# PartsHunter.net
KiCad netlist of a schematic drawn in EAGLE
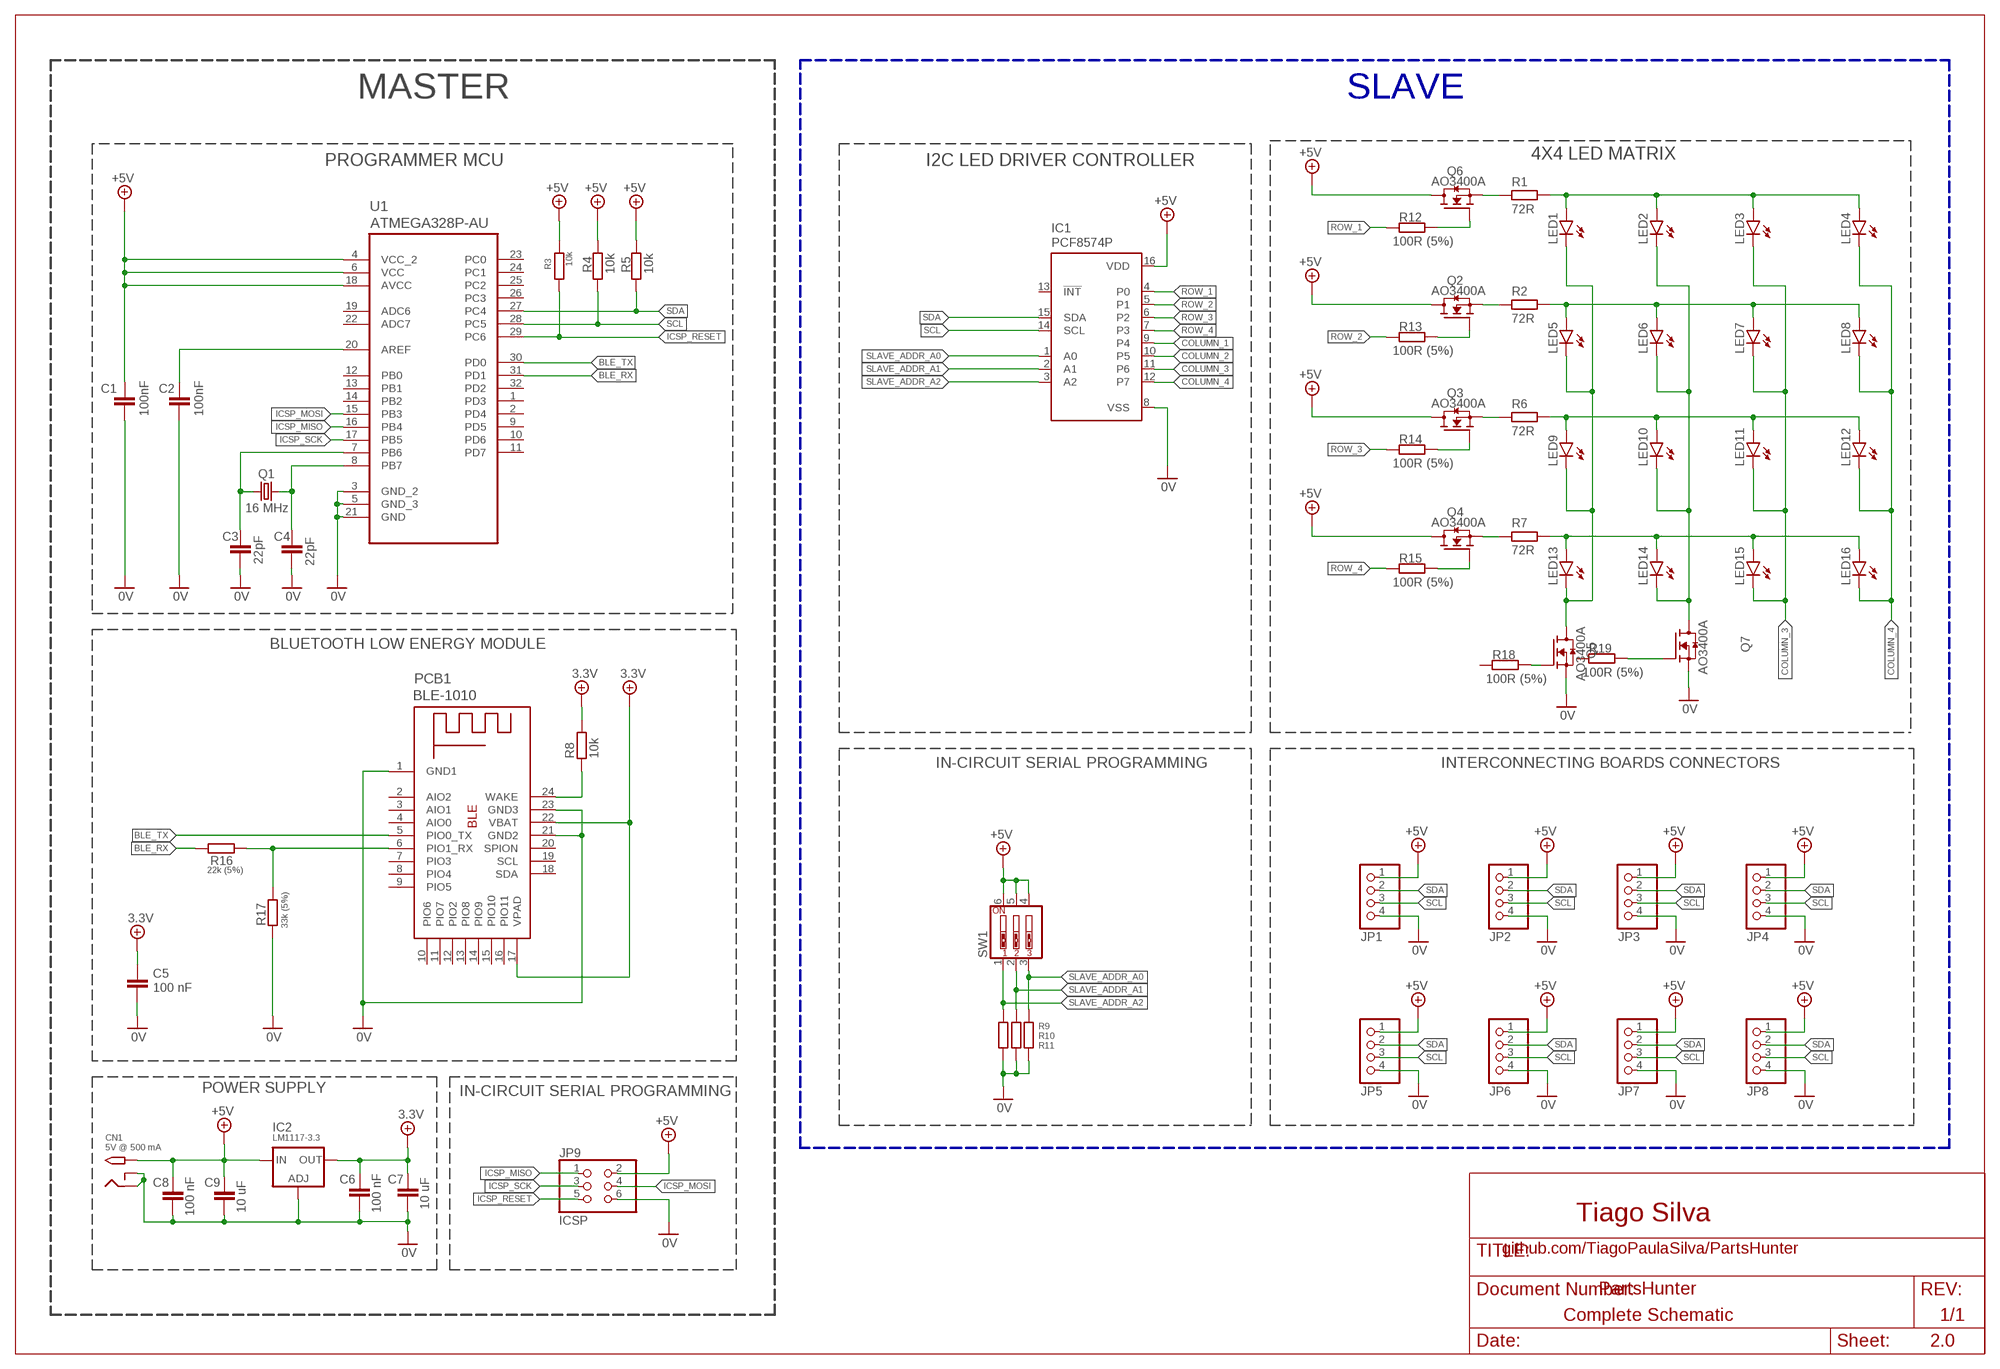
[diagram p0: schematic, sheet 1]

(export (version "E")
  (design (tool "Eeschema 10.0.6"))
  (components
    (comp (ref "C1")
      (value "100nF")
      (footprint "eagle-import:C0805")
      (libsource (lib "eagle-import") (part "C-EUC0805"))
    )
    (comp (ref "C2")
      (value "100nF")
      (footprint "eagle-import:C0805")
      (libsource (lib "eagle-import") (part "C-EUC0805"))
    )
    (comp (ref "C3")
      (value "22pF")
      (footprint "eagle-import:C0805")
      (libsource (lib "eagle-import") (part "C-EUC0805"))
    )
    (comp (ref "C4")
      (value "22pF")
      (footprint "eagle-import:C0805")
      (libsource (lib "eagle-import") (part "C-EUC0805"))
    )
    (comp (ref "C5")
      (value "100 nF")
      (footprint "eagle-import:C0805")
      (libsource (lib "eagle-import") (part "C-EUC0805"))
    )
    (comp (ref "C6")
      (value "100 nF")
      (footprint "eagle-import:C0805")
      (libsource (lib "eagle-import") (part "C-EUC0805"))
    )
    (comp (ref "C7")
      (value "10 uF")
      (footprint "eagle-import:C0805")
      (libsource (lib "eagle-import") (part "C-EUC0805"))
    )
    (comp (ref "C8")
      (value "100 nF")
      (footprint "eagle-import:C0805")
      (libsource (lib "eagle-import") (part "C-EUC0805"))
    )
    (comp (ref "C9")
      (value "10 uF")
      (footprint "eagle-import:C0805")
      (libsource (lib "eagle-import") (part "C-EUC0805"))
    )
    (comp (ref "CN1")
      (value "2.1MMJACKTHM")
      (footprint "eagle-import:PJ-102A")
      (libsource (lib "eagle-import") (part "2.1MMJACKTHM"))
    )
    (comp (ref "IC1")
      (value "PCF8574P")
      (footprint "eagle-import:DIL16")
      (fields (field (name "MPN") "PCF8574PN"))
      (libsource (lib "eagle-import") (part "PCF8574P"))
    )
    (comp (ref "IC2")
      (value "LM1117-3.3")
      (footprint "eagle-import:SOT223")
      (libsource (lib "eagle-import") (part "LD117A?S33TR"))
    )
    (comp (ref "JP1")
      (value "PINHD-1X4/90")
      (footprint "eagle-import:1X04_90")
      (libsource (lib "eagle-import") (part "PINHD-1X4/90"))
    )
    (comp (ref "JP2")
      (value "PINHD-1X4/90")
      (footprint "eagle-import:1X04_90")
      (libsource (lib "eagle-import") (part "PINHD-1X4/90"))
    )
    (comp (ref "JP3")
      (value "PINHD-1X4/90")
      (footprint "eagle-import:1X04_90")
      (libsource (lib "eagle-import") (part "PINHD-1X4/90"))
    )
    (comp (ref "JP4")
      (value "PINHD-1X4/90")
      (footprint "eagle-import:1X04_90")
      (libsource (lib "eagle-import") (part "PINHD-1X4/90"))
    )
    (comp (ref "JP5")
      (value "PINHD-1X4/90")
      (footprint "eagle-import:1X04_90")
      (libsource (lib "eagle-import") (part "PINHD-1X4/90"))
    )
    (comp (ref "JP6")
      (value "PINHD-1X4/90")
      (footprint "eagle-import:1X04_90")
      (libsource (lib "eagle-import") (part "PINHD-1X4/90"))
    )
    (comp (ref "JP7")
      (value "PINHD-1X4/90")
      (footprint "eagle-import:1X04_90")
      (libsource (lib "eagle-import") (part "PINHD-1X4/90"))
    )
    (comp (ref "JP8")
      (value "PINHD-1X4/90")
      (footprint "eagle-import:1X04_90")
      (libsource (lib "eagle-import") (part "PINHD-1X4/90"))
    )
    (comp (ref "JP9")
      (value "ICSP")
      (footprint "eagle-import:2X03")
      (libsource (lib "eagle-import") (part "PINHD-2X3"))
    )
    (comp (ref "LED1")
      (value "LEDKA-3528ASYC")
      (footprint "eagle-import:KA-3528ASYC")
      (libsource (lib "eagle-import") (part "LEDKA-3528ASYC"))
    )
    (comp (ref "LED2")
      (value "LEDKA-3528ASYC")
      (footprint "eagle-import:KA-3528ASYC")
      (libsource (lib "eagle-import") (part "LEDKA-3528ASYC"))
    )
    (comp (ref "LED3")
      (value "LEDKA-3528ASYC")
      (footprint "eagle-import:KA-3528ASYC")
      (libsource (lib "eagle-import") (part "LEDKA-3528ASYC"))
    )
    (comp (ref "LED4")
      (value "LEDKA-3528ASYC")
      (footprint "eagle-import:KA-3528ASYC")
      (libsource (lib "eagle-import") (part "LEDKA-3528ASYC"))
    )
    (comp (ref "LED5")
      (value "LEDKA-3528ASYC")
      (footprint "eagle-import:KA-3528ASYC")
      (libsource (lib "eagle-import") (part "LEDKA-3528ASYC"))
    )
    (comp (ref "LED6")
      (value "LEDKA-3528ASYC")
      (footprint "eagle-import:KA-3528ASYC")
      (libsource (lib "eagle-import") (part "LEDKA-3528ASYC"))
    )
    (comp (ref "LED7")
      (value "LEDKA-3528ASYC")
      (footprint "eagle-import:KA-3528ASYC")
      (libsource (lib "eagle-import") (part "LEDKA-3528ASYC"))
    )
    (comp (ref "LED8")
      (value "LEDKA-3528ASYC")
      (footprint "eagle-import:KA-3528ASYC")
      (libsource (lib "eagle-import") (part "LEDKA-3528ASYC"))
    )
    (comp (ref "LED9")
      (value "LEDKA-3528ASYC")
      (footprint "eagle-import:KA-3528ASYC")
      (libsource (lib "eagle-import") (part "LEDKA-3528ASYC"))
    )
    (comp (ref "LED10")
      (value "LEDKA-3528ASYC")
      (footprint "eagle-import:KA-3528ASYC")
      (libsource (lib "eagle-import") (part "LEDKA-3528ASYC"))
    )
    (comp (ref "LED11")
      (value "LEDKA-3528ASYC")
      (footprint "eagle-import:KA-3528ASYC")
      (libsource (lib "eagle-import") (part "LEDKA-3528ASYC"))
    )
    (comp (ref "LED12")
      (value "LEDKA-3528ASYC")
      (footprint "eagle-import:KA-3528ASYC")
      (libsource (lib "eagle-import") (part "LEDKA-3528ASYC"))
    )
    (comp (ref "LED13")
      (value "LEDKA-3528ASYC")
      (footprint "eagle-import:KA-3528ASYC")
      (libsource (lib "eagle-import") (part "LEDKA-3528ASYC"))
    )
    (comp (ref "LED14")
      (value "LEDKA-3528ASYC")
      (footprint "eagle-import:KA-3528ASYC")
      (libsource (lib "eagle-import") (part "LEDKA-3528ASYC"))
    )
    (comp (ref "LED15")
      (value "LEDKA-3528ASYC")
      (footprint "eagle-import:KA-3528ASYC")
      (libsource (lib "eagle-import") (part "LEDKA-3528ASYC"))
    )
    (comp (ref "LED16")
      (value "LEDKA-3528ASYC")
      (footprint "eagle-import:KA-3528ASYC")
      (libsource (lib "eagle-import") (part "LEDKA-3528ASYC"))
    )
    (comp (ref "PCB1")
      (value "BLE-1010")
      (footprint "eagle-import:BLE-1010")
      (libsource (lib "eagle-import") (part "BLE-1010"))
    )
    (comp (ref "Q1")
      (value "16 MHz")
      (footprint "eagle-import:HC49UP")
      (libsource (lib "eagle-import") (part "CRYSTALHC49UP"))
    )
    (comp (ref "Q2")
      (value "AO3400A")
      (footprint "eagle-import:SOT95P280X125-3N")
      (fields (field (name "MF") "Alpha &"))
      (libsource (lib "eagle-import") (part "AO3400A"))
    )
    (comp (ref "Q3")
      (value "AO3400A")
      (footprint "eagle-import:SOT95P280X125-3N")
      (fields (field (name "MF") "Alpha &"))
      (libsource (lib "eagle-import") (part "AO3400A"))
    )
    (comp (ref "Q4")
      (value "AO3400A")
      (footprint "eagle-import:SOT95P280X125-3N")
      (fields (field (name "MF") "Alpha &"))
      (libsource (lib "eagle-import") (part "AO3400A"))
    )
    (comp (ref "Q5")
      (value "AO3400A")
      (footprint "eagle-import:SOT95P280X125-3N")
      (fields (field (name "MF") "Alpha &"))
      (libsource (lib "eagle-import") (part "AO3400A"))
    )
    (comp (ref "Q6")
      (value "AO3400A")
      (footprint "eagle-import:SOT95P280X125-3N")
      (fields (field (name "MF") "Alpha &"))
      (libsource (lib "eagle-import") (part "AO3400A"))
    )
    (comp (ref "Q7")
      (value "AO3400A")
      (footprint "eagle-import:SOT95P280X125-3N")
      (fields (field (name "MF") "Alpha &"))
      (libsource (lib "eagle-import") (part "AO3400A"))
    )
    (comp (ref "R1")
      (value "72R")
      (footprint "eagle-import:R0805")
      (libsource (lib "eagle-import") (part "R-EU_R0805"))
    )
    (comp (ref "R2")
      (value "72R")
      (footprint "eagle-import:R0805")
      (libsource (lib "eagle-import") (part "R-EU_R0805"))
    )
    (comp (ref "R3")
      (value "10k")
      (footprint "eagle-import:R0805")
      (libsource (lib "eagle-import") (part "R-EU_R0805"))
    )
    (comp (ref "R4")
      (value "10k")
      (footprint "eagle-import:R0805")
      (libsource (lib "eagle-import") (part "R-EU_R0805"))
    )
    (comp (ref "R5")
      (value "10k")
      (footprint "eagle-import:R0805")
      (libsource (lib "eagle-import") (part "R-EU_R0805"))
    )
    (comp (ref "R6")
      (value "72R")
      (footprint "eagle-import:R0805")
      (libsource (lib "eagle-import") (part "R-EU_R0805"))
    )
    (comp (ref "R7")
      (value "72R")
      (footprint "eagle-import:R0805")
      (libsource (lib "eagle-import") (part "R-EU_R0805"))
    )
    (comp (ref "R8")
      (value "10k")
      (footprint "eagle-import:R0603")
      (libsource (lib "eagle-import") (part "R-EU_R0603"))
    )
    (comp (ref "R9")
      (value "10k")
      (footprint "eagle-import:R0805")
      (libsource (lib "eagle-import") (part "R-EU_R0805"))
    )
    (comp (ref "R10")
      (value "10k")
      (footprint "eagle-import:R0805")
      (libsource (lib "eagle-import") (part "R-EU_R0805"))
    )
    (comp (ref "R11")
      (value "10k")
      (footprint "eagle-import:R0805")
      (libsource (lib "eagle-import") (part "R-EU_R0805"))
    )
    (comp (ref "R12")
      (value "100R (5%)")
      (footprint "eagle-import:R0805")
      (libsource (lib "eagle-import") (part "R-EU_R0805"))
    )
    (comp (ref "R13")
      (value "100R (5%)")
      (footprint "eagle-import:R0805")
      (libsource (lib "eagle-import") (part "R-EU_R0805"))
    )
    (comp (ref "R14")
      (value "100R (5%)")
      (footprint "eagle-import:R0805")
      (libsource (lib "eagle-import") (part "R-EU_R0805"))
    )
    (comp (ref "R15")
      (value "100R (5%)")
      (footprint "eagle-import:R0805")
      (libsource (lib "eagle-import") (part "R-EU_R0805"))
    )
    (comp (ref "R16")
      (value "22k (5%)")
      (footprint "eagle-import:R0805")
      (libsource (lib "eagle-import") (part "R-EU_R0805"))
    )
    (comp (ref "R17")
      (value "33k (5%)")
      (footprint "eagle-import:R0805")
      (libsource (lib "eagle-import") (part "R-EU_R0805"))
    )
    (comp (ref "R18")
      (value "100R (5%)")
      (footprint "eagle-import:R0805")
      (libsource (lib "eagle-import") (part "R-EU_R0805"))
    )
    (comp (ref "R19")
      (value "100R (5%)")
      (footprint "eagle-import:R0805")
      (libsource (lib "eagle-import") (part "R-EU_R0805"))
    )
    (comp (ref "SW1")
      (value "SW_DIP-3")
      (footprint "eagle-import:EDG-03")
      (libsource (lib "eagle-import") (part "SW_DIP-3"))
    )
    (comp (ref "U1")
      (value "ATMEGA328P-AU")
      (footprint "eagle-import:QFP80P900X900X120-32N")
      (libsource (lib "eagle-import") (part "ATMEGA328P-AU"))
    )
  )
  (nets
    (net (code "1") (name "+5V") (class "Default")
      (node (ref "C1") (pin "2") (pinfunction "2_2") (pintype "passive"))
      (node (ref "C8") (pin "1") (pinfunction "1_1") (pintype "passive"))
      (node (ref "C9") (pin "1") (pinfunction "1_1") (pintype "passive"))
      (node (ref "CN1") (pin "TIP") (pinfunction "TIP_TIP") (pintype "bidirectional"))
      (node (ref "IC1") (pin "16") (pinfunction "VDD_16") (pintype "power_in"))
      (node (ref "IC2") (pin "3") (pinfunction "IN_3") (pintype "input"))
      (node (ref "JP1") (pin "1") (pinfunction "1_1") (pintype "passive"))
      (node (ref "JP2") (pin "1") (pinfunction "1_1") (pintype "passive"))
      (node (ref "JP3") (pin "1") (pinfunction "1_1") (pintype "passive"))
      (node (ref "JP4") (pin "1") (pinfunction "1_1") (pintype "passive"))
      (node (ref "JP5") (pin "1") (pinfunction "1_1") (pintype "passive"))
      (node (ref "JP6") (pin "1") (pinfunction "1_1") (pintype "passive"))
      (node (ref "JP7") (pin "1") (pinfunction "1_1") (pintype "passive"))
      (node (ref "JP8") (pin "1") (pinfunction "1_1") (pintype "passive"))
      (node (ref "JP9") (pin "2") (pinfunction "2_2") (pintype "passive"))
      (node (ref "Q2") (pin "3") (pinfunction "D_3") (pintype "passive"))
      (node (ref "Q3") (pin "3") (pinfunction "D_3") (pintype "passive"))
      (node (ref "Q4") (pin "3") (pinfunction "D_3") (pintype "passive"))
      (node (ref "Q6") (pin "3") (pinfunction "D_3") (pintype "passive"))
      (node (ref "R3") (pin "1") (pinfunction "1_1") (pintype "passive"))
      (node (ref "R4") (pin "1") (pinfunction "1_1") (pintype "passive"))
      (node (ref "R5") (pin "1") (pinfunction "1_1") (pintype "passive"))
      (node (ref "SW1") (pin "4") (pinfunction "4_4") (pintype "passive"))
      (node (ref "SW1") (pin "5") (pinfunction "5_5") (pintype "passive"))
      (node (ref "SW1") (pin "6") (pinfunction "6_6") (pintype "passive"))
      (node (ref "U1") (pin "18") (pinfunction "AVCC_18") (pintype "power_in"))
      (node (ref "U1") (pin "4") (pinfunction "VCC_2_4") (pintype "power_in"))
      (node (ref "U1") (pin "6") (pinfunction "VCC_6") (pintype "power_in"))
    )
    (net (code "2") (name "0V") (class "Default")
      (node (ref "C1") (pin "1") (pinfunction "1_1") (pintype "passive"))
      (node (ref "C2") (pin "1") (pinfunction "1_1") (pintype "passive"))
      (node (ref "C3") (pin "1") (pinfunction "1_1") (pintype "passive"))
      (node (ref "C4") (pin "1") (pinfunction "1_1") (pintype "passive"))
      (node (ref "C5") (pin "2") (pinfunction "2_2") (pintype "passive"))
      (node (ref "C6") (pin "2") (pinfunction "2_2") (pintype "passive"))
      (node (ref "C7") (pin "2") (pinfunction "2_2") (pintype "passive"))
      (node (ref "C8") (pin "2") (pinfunction "2_2") (pintype "passive"))
      (node (ref "C9") (pin "2") (pinfunction "2_2") (pintype "passive"))
      (node (ref "CN1") (pin "RING") (pinfunction "RING_RING") (pintype "bidirectional"))
      (node (ref "CN1") (pin "RING_SW") (pinfunction "RING_SW_RING_SW") (pintype "bidirectional"))
      (node (ref "IC1") (pin "8") (pinfunction "VSS_8") (pintype "power_in"))
      (node (ref "IC2") (pin "1") (pinfunction "ADJ_1") (pintype "input"))
      (node (ref "JP1") (pin "4") (pinfunction "4_4") (pintype "passive"))
      (node (ref "JP2") (pin "4") (pinfunction "4_4") (pintype "passive"))
      (node (ref "JP3") (pin "4") (pinfunction "4_4") (pintype "passive"))
      (node (ref "JP4") (pin "4") (pinfunction "4_4") (pintype "passive"))
      (node (ref "JP5") (pin "4") (pinfunction "4_4") (pintype "passive"))
      (node (ref "JP6") (pin "4") (pinfunction "4_4") (pintype "passive"))
      (node (ref "JP7") (pin "4") (pinfunction "4_4") (pintype "passive"))
      (node (ref "JP8") (pin "4") (pinfunction "4_4") (pintype "passive"))
      (node (ref "JP9") (pin "6") (pinfunction "6_6") (pintype "passive"))
      (node (ref "PCB1") (pin "1") (pinfunction "GND1_1") (pintype "power_in"))
      (node (ref "PCB1") (pin "21") (pinfunction "GND2_21") (pintype "power_in"))
      (node (ref "PCB1") (pin "23") (pinfunction "GND3_23") (pintype "power_in"))
      (node (ref "Q5") (pin "2") (pinfunction "S_2") (pintype "passive"))
      (node (ref "Q7") (pin "2") (pinfunction "S_2") (pintype "passive"))
      (node (ref "R10") (pin "2") (pinfunction "2_2") (pintype "passive"))
      (node (ref "R11") (pin "2") (pinfunction "2_2") (pintype "passive"))
      (node (ref "R17") (pin "1") (pinfunction "1_1") (pintype "passive"))
      (node (ref "R9") (pin "2") (pinfunction "2_2") (pintype "passive"))
      (node (ref "U1") (pin "21") (pinfunction "GND_21") (pintype "passive"))
      (node (ref "U1") (pin "3") (pinfunction "GND_2_3") (pintype "passive"))
      (node (ref "U1") (pin "5") (pinfunction "GND_3_5") (pintype "passive"))
    )
    (net (code "3") (name "3.3V") (class "Default")
      (node (ref "C5") (pin "1") (pinfunction "1_1") (pintype "passive"))
      (node (ref "C6") (pin "1") (pinfunction "1_1") (pintype "passive"))
      (node (ref "C7") (pin "1") (pinfunction "1_1") (pintype "passive"))
      (node (ref "IC2") (pin "4") (pinfunction "OUT_4") (pintype "passive"))
      (node (ref "PCB1") (pin "17") (pinfunction "VPAD_17") (pintype "bidirectional"))
      (node (ref "PCB1") (pin "22") (pinfunction "VBAT_22") (pintype "power_in"))
      (node (ref "R8") (pin "1") (pinfunction "1_1") (pintype "passive"))
    )
    (net (code "4") (name "BLE_RX") (class "Default")
      (node (ref "R16") (pin "1") (pinfunction "1_1") (pintype "passive"))
      (node (ref "U1") (pin "31") (pinfunction "PD1_31") (pintype "bidirectional"))
    )
    (net (code "5") (name "BLE_TX") (class "Default")
      (node (ref "PCB1") (pin "5") (pinfunction "PIO0_TX_5") (pintype "bidirectional"))
      (node (ref "U1") (pin "30") (pinfunction "PD0_30") (pintype "bidirectional"))
    )
    (net (code "6") (name "COLUMN_1") (class "Default")
      (node (ref "IC1") (pin "9") (pinfunction "P4_9") (pintype "bidirectional"))
      (node (ref "LED1") (pin "C") (pinfunction "C_C") (pintype "passive"))
      (node (ref "LED1") (pin "P$2") (pinfunction "C_P$2") (pintype "passive"))
      (node (ref "LED13") (pin "C") (pinfunction "C_C") (pintype "passive"))
      (node (ref "LED13") (pin "P$2") (pinfunction "C_P$2") (pintype "passive"))
      (node (ref "LED5") (pin "C") (pinfunction "C_C") (pintype "passive"))
      (node (ref "LED5") (pin "P$2") (pinfunction "C_P$2") (pintype "passive"))
      (node (ref "LED9") (pin "C") (pinfunction "C_C") (pintype "passive"))
      (node (ref "LED9") (pin "P$2") (pinfunction "C_P$2") (pintype "passive"))
      (node (ref "Q5") (pin "3") (pinfunction "D_3") (pintype "passive"))
    )
    (net (code "7") (name "COLUMN_2") (class "Default")
      (node (ref "IC1") (pin "10") (pinfunction "P5_10") (pintype "bidirectional"))
      (node (ref "LED10") (pin "C") (pinfunction "C_C") (pintype "passive"))
      (node (ref "LED10") (pin "P$2") (pinfunction "C_P$2") (pintype "passive"))
      (node (ref "LED14") (pin "C") (pinfunction "C_C") (pintype "passive"))
      (node (ref "LED14") (pin "P$2") (pinfunction "C_P$2") (pintype "passive"))
      (node (ref "LED2") (pin "C") (pinfunction "C_C") (pintype "passive"))
      (node (ref "LED2") (pin "P$2") (pinfunction "C_P$2") (pintype "passive"))
      (node (ref "LED6") (pin "C") (pinfunction "C_C") (pintype "passive"))
      (node (ref "LED6") (pin "P$2") (pinfunction "C_P$2") (pintype "passive"))
      (node (ref "Q7") (pin "3") (pinfunction "D_3") (pintype "passive"))
    )
    (net (code "8") (name "COLUMN_3") (class "Default")
      (node (ref "IC1") (pin "11") (pinfunction "P6_11") (pintype "bidirectional"))
      (node (ref "LED11") (pin "C") (pinfunction "C_C") (pintype "passive"))
      (node (ref "LED11") (pin "P$2") (pinfunction "C_P$2") (pintype "passive"))
      (node (ref "LED15") (pin "C") (pinfunction "C_C") (pintype "passive"))
      (node (ref "LED15") (pin "P$2") (pinfunction "C_P$2") (pintype "passive"))
      (node (ref "LED3") (pin "C") (pinfunction "C_C") (pintype "passive"))
      (node (ref "LED3") (pin "P$2") (pinfunction "C_P$2") (pintype "passive"))
      (node (ref "LED7") (pin "C") (pinfunction "C_C") (pintype "passive"))
      (node (ref "LED7") (pin "P$2") (pinfunction "C_P$2") (pintype "passive"))
    )
    (net (code "9") (name "COLUMN_4") (class "Default")
      (node (ref "IC1") (pin "12") (pinfunction "P7_12") (pintype "bidirectional"))
      (node (ref "LED12") (pin "C") (pinfunction "C_C") (pintype "passive"))
      (node (ref "LED12") (pin "P$2") (pinfunction "C_P$2") (pintype "passive"))
      (node (ref "LED16") (pin "C") (pinfunction "C_C") (pintype "passive"))
      (node (ref "LED16") (pin "P$2") (pinfunction "C_P$2") (pintype "passive"))
      (node (ref "LED4") (pin "C") (pinfunction "C_C") (pintype "passive"))
      (node (ref "LED4") (pin "P$2") (pinfunction "C_P$2") (pintype "passive"))
      (node (ref "LED8") (pin "C") (pinfunction "C_C") (pintype "passive"))
      (node (ref "LED8") (pin "P$2") (pinfunction "C_P$2") (pintype "passive"))
    )
    (net (code "10") (name "ICSP_MISO") (class "Default")
      (node (ref "JP9") (pin "1") (pinfunction "1_1") (pintype "passive"))
      (node (ref "U1") (pin "16") (pinfunction "PB4_16") (pintype "bidirectional"))
    )
    (net (code "11") (name "ICSP_MOSI") (class "Default")
      (node (ref "JP9") (pin "4") (pinfunction "4_4") (pintype "passive"))
      (node (ref "U1") (pin "15") (pinfunction "PB3_15") (pintype "bidirectional"))
    )
    (net (code "12") (name "ICSP_RESET") (class "Default")
      (node (ref "JP9") (pin "5") (pinfunction "5_5") (pintype "passive"))
      (node (ref "R3") (pin "2") (pinfunction "2_2") (pintype "passive"))
      (node (ref "U1") (pin "29") (pinfunction "PC6_29") (pintype "bidirectional"))
    )
    (net (code "13") (name "ICSP_SCK") (class "Default")
      (node (ref "JP9") (pin "3") (pinfunction "3_3") (pintype "passive"))
      (node (ref "U1") (pin "17") (pinfunction "PB5_17") (pintype "bidirectional"))
    )
    (net (code "14") (name "Net-(LED1-A-PadP$1)") (class "Default")
      (node (ref "LED1") (pin "A") (pinfunction "A_A") (pintype "passive"))
      (node (ref "LED1") (pin "P$1") (pinfunction "A_P$1") (pintype "passive"))
      (node (ref "LED2") (pin "A") (pinfunction "A_A") (pintype "passive"))
      (node (ref "LED2") (pin "P$1") (pinfunction "A_P$1") (pintype "passive"))
      (node (ref "LED3") (pin "A") (pinfunction "A_A") (pintype "passive"))
      (node (ref "LED3") (pin "P$1") (pinfunction "A_P$1") (pintype "passive"))
      (node (ref "LED4") (pin "A") (pinfunction "A_A") (pintype "passive"))
      (node (ref "LED4") (pin "P$1") (pinfunction "A_P$1") (pintype "passive"))
      (node (ref "R1") (pin "1") (pinfunction "1_1") (pintype "passive"))
    )
    (net (code "15") (name "Net-(LED5-A-PadP$1)") (class "Default")
      (node (ref "LED5") (pin "A") (pinfunction "A_A") (pintype "passive"))
      (node (ref "LED5") (pin "P$1") (pinfunction "A_P$1") (pintype "passive"))
      (node (ref "LED6") (pin "A") (pinfunction "A_A") (pintype "passive"))
      (node (ref "LED6") (pin "P$1") (pinfunction "A_P$1") (pintype "passive"))
      (node (ref "LED7") (pin "A") (pinfunction "A_A") (pintype "passive"))
      (node (ref "LED7") (pin "P$1") (pinfunction "A_P$1") (pintype "passive"))
      (node (ref "LED8") (pin "A") (pinfunction "A_A") (pintype "passive"))
      (node (ref "LED8") (pin "P$1") (pinfunction "A_P$1") (pintype "passive"))
      (node (ref "R2") (pin "1") (pinfunction "1_1") (pintype "passive"))
    )
    (net (code "16") (name "Net-(LED10-A-PadP$1)") (class "Default")
      (node (ref "LED10") (pin "A") (pinfunction "A_A") (pintype "passive"))
      (node (ref "LED10") (pin "P$1") (pinfunction "A_P$1") (pintype "passive"))
      (node (ref "LED11") (pin "A") (pinfunction "A_A") (pintype "passive"))
      (node (ref "LED11") (pin "P$1") (pinfunction "A_P$1") (pintype "passive"))
      (node (ref "LED12") (pin "A") (pinfunction "A_A") (pintype "passive"))
      (node (ref "LED12") (pin "P$1") (pinfunction "A_P$1") (pintype "passive"))
      (node (ref "LED9") (pin "A") (pinfunction "A_A") (pintype "passive"))
      (node (ref "LED9") (pin "P$1") (pinfunction "A_P$1") (pintype "passive"))
      (node (ref "R6") (pin "1") (pinfunction "1_1") (pintype "passive"))
    )
    (net (code "17") (name "Net-(LED13-A-PadP$1)") (class "Default")
      (node (ref "LED13") (pin "A") (pinfunction "A_A") (pintype "passive"))
      (node (ref "LED13") (pin "P$1") (pinfunction "A_P$1") (pintype "passive"))
      (node (ref "LED14") (pin "A") (pinfunction "A_A") (pintype "passive"))
      (node (ref "LED14") (pin "P$1") (pinfunction "A_P$1") (pintype "passive"))
      (node (ref "LED15") (pin "A") (pinfunction "A_A") (pintype "passive"))
      (node (ref "LED15") (pin "P$1") (pinfunction "A_P$1") (pintype "passive"))
      (node (ref "LED16") (pin "A") (pinfunction "A_A") (pintype "passive"))
      (node (ref "LED16") (pin "P$1") (pinfunction "A_P$1") (pintype "passive"))
      (node (ref "R7") (pin "1") (pinfunction "1_1") (pintype "passive"))
    )
    (net (code "18") (name "Net-(PCB1-PIO1_RX)") (class "Default")
      (node (ref "PCB1") (pin "6") (pinfunction "PIO1_RX_6") (pintype "bidirectional"))
      (node (ref "R16") (pin "2") (pinfunction "2_2") (pintype "passive"))
      (node (ref "R17") (pin "2") (pinfunction "2_2") (pintype "passive"))
    )
    (net (code "19") (name "Net-(PCB1-WAKE)") (class "Default")
      (node (ref "PCB1") (pin "24") (pinfunction "WAKE_24") (pintype "input"))
      (node (ref "R8") (pin "2") (pinfunction "2_2") (pintype "passive"))
    )
    (net (code "20") (name "Net-(Q2-G)") (class "Default")
      (node (ref "Q2") (pin "1") (pinfunction "G_1") (pintype "passive"))
      (node (ref "R13") (pin "2") (pinfunction "2_2") (pintype "passive"))
    )
    (net (code "21") (name "Net-(Q2-S)") (class "Default")
      (node (ref "Q2") (pin "2") (pinfunction "S_2") (pintype "passive"))
      (node (ref "R2") (pin "2") (pinfunction "2_2") (pintype "passive"))
    )
    (net (code "22") (name "Net-(Q3-G)") (class "Default")
      (node (ref "Q3") (pin "1") (pinfunction "G_1") (pintype "passive"))
      (node (ref "R14") (pin "2") (pinfunction "2_2") (pintype "passive"))
    )
    (net (code "23") (name "Net-(Q3-S)") (class "Default")
      (node (ref "Q3") (pin "2") (pinfunction "S_2") (pintype "passive"))
      (node (ref "R6") (pin "2") (pinfunction "2_2") (pintype "passive"))
    )
    (net (code "24") (name "Net-(Q4-G)") (class "Default")
      (node (ref "Q4") (pin "1") (pinfunction "G_1") (pintype "passive"))
      (node (ref "R15") (pin "2") (pinfunction "2_2") (pintype "passive"))
    )
    (net (code "25") (name "Net-(Q4-S)") (class "Default")
      (node (ref "Q4") (pin "2") (pinfunction "S_2") (pintype "passive"))
      (node (ref "R7") (pin "2") (pinfunction "2_2") (pintype "passive"))
    )
    (net (code "26") (name "Net-(Q5-G)") (class "Default")
      (node (ref "Q5") (pin "1") (pinfunction "G_1") (pintype "passive"))
      (node (ref "R18") (pin "2") (pinfunction "2_2") (pintype "passive"))
    )
    (net (code "27") (name "Net-(Q6-G)") (class "Default")
      (node (ref "Q6") (pin "1") (pinfunction "G_1") (pintype "passive"))
      (node (ref "R12") (pin "2") (pinfunction "2_2") (pintype "passive"))
    )
    (net (code "28") (name "Net-(Q6-S)") (class "Default")
      (node (ref "Q6") (pin "2") (pinfunction "S_2") (pintype "passive"))
      (node (ref "R1") (pin "2") (pinfunction "2_2") (pintype "passive"))
    )
    (net (code "29") (name "Net-(Q7-G)") (class "Default")
      (node (ref "Q7") (pin "1") (pinfunction "G_1") (pintype "passive"))
      (node (ref "R19") (pin "2") (pinfunction "2_2") (pintype "passive"))
    )
    (net (code "30") (name "Net-(U1-AREF)") (class "Default")
      (node (ref "C2") (pin "2") (pinfunction "2_2") (pintype "passive"))
      (node (ref "U1") (pin "20") (pinfunction "AREF_20") (pintype "input"))
    )
    (net (code "31") (name "Net-(U1-PB6)") (class "Default")
      (node (ref "C3") (pin "2") (pinfunction "2_2") (pintype "passive"))
      (node (ref "Q1") (pin "1") (pinfunction "1_1") (pintype "passive"))
      (node (ref "U1") (pin "7") (pinfunction "PB6_7") (pintype "bidirectional"))
    )
    (net (code "32") (name "Net-(U1-PB7)") (class "Default")
      (node (ref "C4") (pin "2") (pinfunction "2_2") (pintype "passive"))
      (node (ref "Q1") (pin "2") (pinfunction "2_2") (pintype "passive"))
      (node (ref "U1") (pin "8") (pinfunction "PB7_8") (pintype "bidirectional"))
    )
    (net (code "33") (name "ROW_1") (class "Default")
      (node (ref "IC1") (pin "4") (pinfunction "P0_4") (pintype "bidirectional"))
      (node (ref "R12") (pin "1") (pinfunction "1_1") (pintype "passive"))
    )
    (net (code "34") (name "ROW_2") (class "Default")
      (node (ref "IC1") (pin "5") (pinfunction "P1_5") (pintype "bidirectional"))
      (node (ref "R13") (pin "1") (pinfunction "1_1") (pintype "passive"))
    )
    (net (code "35") (name "ROW_3") (class "Default")
      (node (ref "IC1") (pin "6") (pinfunction "P2_6") (pintype "bidirectional"))
      (node (ref "R14") (pin "1") (pinfunction "1_1") (pintype "passive"))
    )
    (net (code "36") (name "ROW_4") (class "Default")
      (node (ref "IC1") (pin "7") (pinfunction "P3_7") (pintype "bidirectional"))
      (node (ref "R15") (pin "1") (pinfunction "1_1") (pintype "passive"))
    )
    (net (code "37") (name "SCL") (class "Default")
      (node (ref "IC1") (pin "14") (pinfunction "SCL_14") (pintype "input"))
      (node (ref "JP1") (pin "3") (pinfunction "3_3") (pintype "passive"))
      (node (ref "JP2") (pin "3") (pinfunction "3_3") (pintype "passive"))
      (node (ref "JP3") (pin "3") (pinfunction "3_3") (pintype "passive"))
      (node (ref "JP4") (pin "3") (pinfunction "3_3") (pintype "passive"))
      (node (ref "JP5") (pin "3") (pinfunction "3_3") (pintype "passive"))
      (node (ref "JP6") (pin "3") (pinfunction "3_3") (pintype "passive"))
      (node (ref "JP7") (pin "3") (pinfunction "3_3") (pintype "passive"))
      (node (ref "JP8") (pin "3") (pinfunction "3_3") (pintype "passive"))
      (node (ref "R4") (pin "2") (pinfunction "2_2") (pintype "passive"))
      (node (ref "U1") (pin "28") (pinfunction "PC5_28") (pintype "bidirectional"))
    )
    (net (code "38") (name "SDA") (class "Default")
      (node (ref "IC1") (pin "15") (pinfunction "SDA_15") (pintype "bidirectional"))
      (node (ref "JP1") (pin "2") (pinfunction "2_2") (pintype "passive"))
      (node (ref "JP2") (pin "2") (pinfunction "2_2") (pintype "passive"))
      (node (ref "JP3") (pin "2") (pinfunction "2_2") (pintype "passive"))
      (node (ref "JP4") (pin "2") (pinfunction "2_2") (pintype "passive"))
      (node (ref "JP5") (pin "2") (pinfunction "2_2") (pintype "passive"))
      (node (ref "JP6") (pin "2") (pinfunction "2_2") (pintype "passive"))
      (node (ref "JP7") (pin "2") (pinfunction "2_2") (pintype "passive"))
      (node (ref "JP8") (pin "2") (pinfunction "2_2") (pintype "passive"))
      (node (ref "R5") (pin "2") (pinfunction "2_2") (pintype "passive"))
      (node (ref "U1") (pin "27") (pinfunction "PC4_27") (pintype "bidirectional"))
    )
    (net (code "39") (name "SLAVE_ADDR_A0") (class "Default")
      (node (ref "IC1") (pin "1") (pinfunction "A0_1") (pintype "input"))
      (node (ref "R11") (pin "1") (pinfunction "1_1") (pintype "passive"))
      (node (ref "SW1") (pin "3") (pinfunction "3_3") (pintype "passive"))
    )
    (net (code "40") (name "SLAVE_ADDR_A1") (class "Default")
      (node (ref "IC1") (pin "2") (pinfunction "A1_2") (pintype "input"))
      (node (ref "R10") (pin "1") (pinfunction "1_1") (pintype "passive"))
      (node (ref "SW1") (pin "2") (pinfunction "2_2") (pintype "passive"))
    )
    (net (code "41") (name "SLAVE_ADDR_A2") (class "Default")
      (node (ref "IC1") (pin "3") (pinfunction "A2_3") (pintype "input"))
      (node (ref "R9") (pin "1") (pinfunction "1_1") (pintype "passive"))
      (node (ref "SW1") (pin "1") (pinfunction "1_1") (pintype "passive"))
    )
    (net (code "42") (name "unconnected-(IC1-~{INT}-Pad13)") (class "Default")
      (node (ref "IC1") (pin "13") (pinfunction "~{INT}_13") (pintype "output"))
    )
    (net (code "43") (name "unconnected-(PCB1-AIO0-Pad4)") (class "Default")
      (node (ref "PCB1") (pin "4") (pinfunction "AIO0_4") (pintype "bidirectional"))
    )
    (net (code "44") (name "unconnected-(PCB1-AIO1-Pad3)") (class "Default")
      (node (ref "PCB1") (pin "3") (pinfunction "AIO1_3") (pintype "bidirectional"))
    )
    (net (code "45") (name "unconnected-(PCB1-AIO2-Pad2)") (class "Default")
      (node (ref "PCB1") (pin "2") (pinfunction "AIO2_2") (pintype "bidirectional"))
    )
    (net (code "46") (name "unconnected-(PCB1-PIO2-Pad12)") (class "Default")
      (node (ref "PCB1") (pin "12") (pinfunction "PIO2_12") (pintype "bidirectional"))
    )
    (net (code "47") (name "unconnected-(PCB1-PIO3-Pad7)") (class "Default")
      (node (ref "PCB1") (pin "7") (pinfunction "PIO3_7") (pintype "bidirectional"))
    )
    (net (code "48") (name "unconnected-(PCB1-PIO4-Pad8)") (class "Default")
      (node (ref "PCB1") (pin "8") (pinfunction "PIO4_8") (pintype "bidirectional"))
    )
    (net (code "49") (name "unconnected-(PCB1-PIO5-Pad9)") (class "Default")
      (node (ref "PCB1") (pin "9") (pinfunction "PIO5_9") (pintype "bidirectional"))
    )
    (net (code "50") (name "unconnected-(PCB1-PIO6-Pad10)") (class "Default")
      (node (ref "PCB1") (pin "10") (pinfunction "PIO6_10") (pintype "bidirectional"))
    )
    (net (code "51") (name "unconnected-(PCB1-PIO7-Pad11)") (class "Default")
      (node (ref "PCB1") (pin "11") (pinfunction "PIO7_11") (pintype "bidirectional"))
    )
    (net (code "52") (name "unconnected-(PCB1-PIO8-Pad13)") (class "Default")
      (node (ref "PCB1") (pin "13") (pinfunction "PIO8_13") (pintype "bidirectional"))
    )
    (net (code "53") (name "unconnected-(PCB1-PIO9-Pad14)") (class "Default")
      (node (ref "PCB1") (pin "14") (pinfunction "PIO9_14") (pintype "bidirectional"))
    )
    (net (code "54") (name "unconnected-(PCB1-PIO10-Pad15)") (class "Default")
      (node (ref "PCB1") (pin "15") (pinfunction "PIO10_15") (pintype "bidirectional"))
    )
    (net (code "55") (name "unconnected-(PCB1-PIO11-Pad16)") (class "Default")
      (node (ref "PCB1") (pin "16") (pinfunction "PIO11_16") (pintype "bidirectional"))
    )
    (net (code "56") (name "unconnected-(PCB1-SCL-Pad19)") (class "Default")
      (node (ref "PCB1") (pin "19") (pinfunction "SCL_19") (pintype "bidirectional"))
    )
    (net (code "57") (name "unconnected-(PCB1-SDA-Pad18)") (class "Default")
      (node (ref "PCB1") (pin "18") (pinfunction "SDA_18") (pintype "bidirectional"))
    )
    (net (code "58") (name "unconnected-(PCB1-SPION-Pad20)") (class "Default")
      (node (ref "PCB1") (pin "20") (pinfunction "SPION_20") (pintype "bidirectional"))
    )
    (net (code "59") (name "unconnected-(R18-Pad1)") (class "Default")
      (node (ref "R18") (pin "1") (pinfunction "1_1") (pintype "passive"))
    )
    (net (code "60") (name "unconnected-(R19-Pad1)") (class "Default")
      (node (ref "R19") (pin "1") (pinfunction "1_1") (pintype "passive"))
    )
    (net (code "61") (name "unconnected-(U1-ADC6-Pad19)") (class "Default")
      (node (ref "U1") (pin "19") (pinfunction "ADC6_19") (pintype "input"))
    )
    (net (code "62") (name "unconnected-(U1-ADC7-Pad22)") (class "Default")
      (node (ref "U1") (pin "22") (pinfunction "ADC7_22") (pintype "input"))
    )
    (net (code "63") (name "unconnected-(U1-PB0-Pad12)") (class "Default")
      (node (ref "U1") (pin "12") (pinfunction "PB0_12") (pintype "bidirectional"))
    )
    (net (code "64") (name "unconnected-(U1-PB1-Pad13)") (class "Default")
      (node (ref "U1") (pin "13") (pinfunction "PB1_13") (pintype "bidirectional"))
    )
    (net (code "65") (name "unconnected-(U1-PB2-Pad14)") (class "Default")
      (node (ref "U1") (pin "14") (pinfunction "PB2_14") (pintype "bidirectional"))
    )
    (net (code "66") (name "unconnected-(U1-PC0-Pad23)") (class "Default")
      (node (ref "U1") (pin "23") (pinfunction "PC0_23") (pintype "bidirectional"))
    )
    (net (code "67") (name "unconnected-(U1-PC1-Pad24)") (class "Default")
      (node (ref "U1") (pin "24") (pinfunction "PC1_24") (pintype "bidirectional"))
    )
    (net (code "68") (name "unconnected-(U1-PC2-Pad25)") (class "Default")
      (node (ref "U1") (pin "25") (pinfunction "PC2_25") (pintype "bidirectional"))
    )
    (net (code "69") (name "unconnected-(U1-PC3-Pad26)") (class "Default")
      (node (ref "U1") (pin "26") (pinfunction "PC3_26") (pintype "bidirectional"))
    )
    (net (code "70") (name "unconnected-(U1-PD2-Pad32)") (class "Default")
      (node (ref "U1") (pin "32") (pinfunction "PD2_32") (pintype "bidirectional"))
    )
    (net (code "71") (name "unconnected-(U1-PD3-Pad1)") (class "Default")
      (node (ref "U1") (pin "1") (pinfunction "PD3_1") (pintype "bidirectional"))
    )
    (net (code "72") (name "unconnected-(U1-PD4-Pad2)") (class "Default")
      (node (ref "U1") (pin "2") (pinfunction "PD4_2") (pintype "bidirectional"))
    )
    (net (code "73") (name "unconnected-(U1-PD5-Pad9)") (class "Default")
      (node (ref "U1") (pin "9") (pinfunction "PD5_9") (pintype "bidirectional"))
    )
    (net (code "74") (name "unconnected-(U1-PD6-Pad10)") (class "Default")
      (node (ref "U1") (pin "10") (pinfunction "PD6_10") (pintype "bidirectional"))
    )
    (net (code "75") (name "unconnected-(U1-PD7-Pad11)") (class "Default")
      (node (ref "U1") (pin "11") (pinfunction "PD7_11") (pintype "bidirectional"))
    )
  )
)
